# FPGA-8.net
KiCad netlist of a schematic drawn in Altium Designer
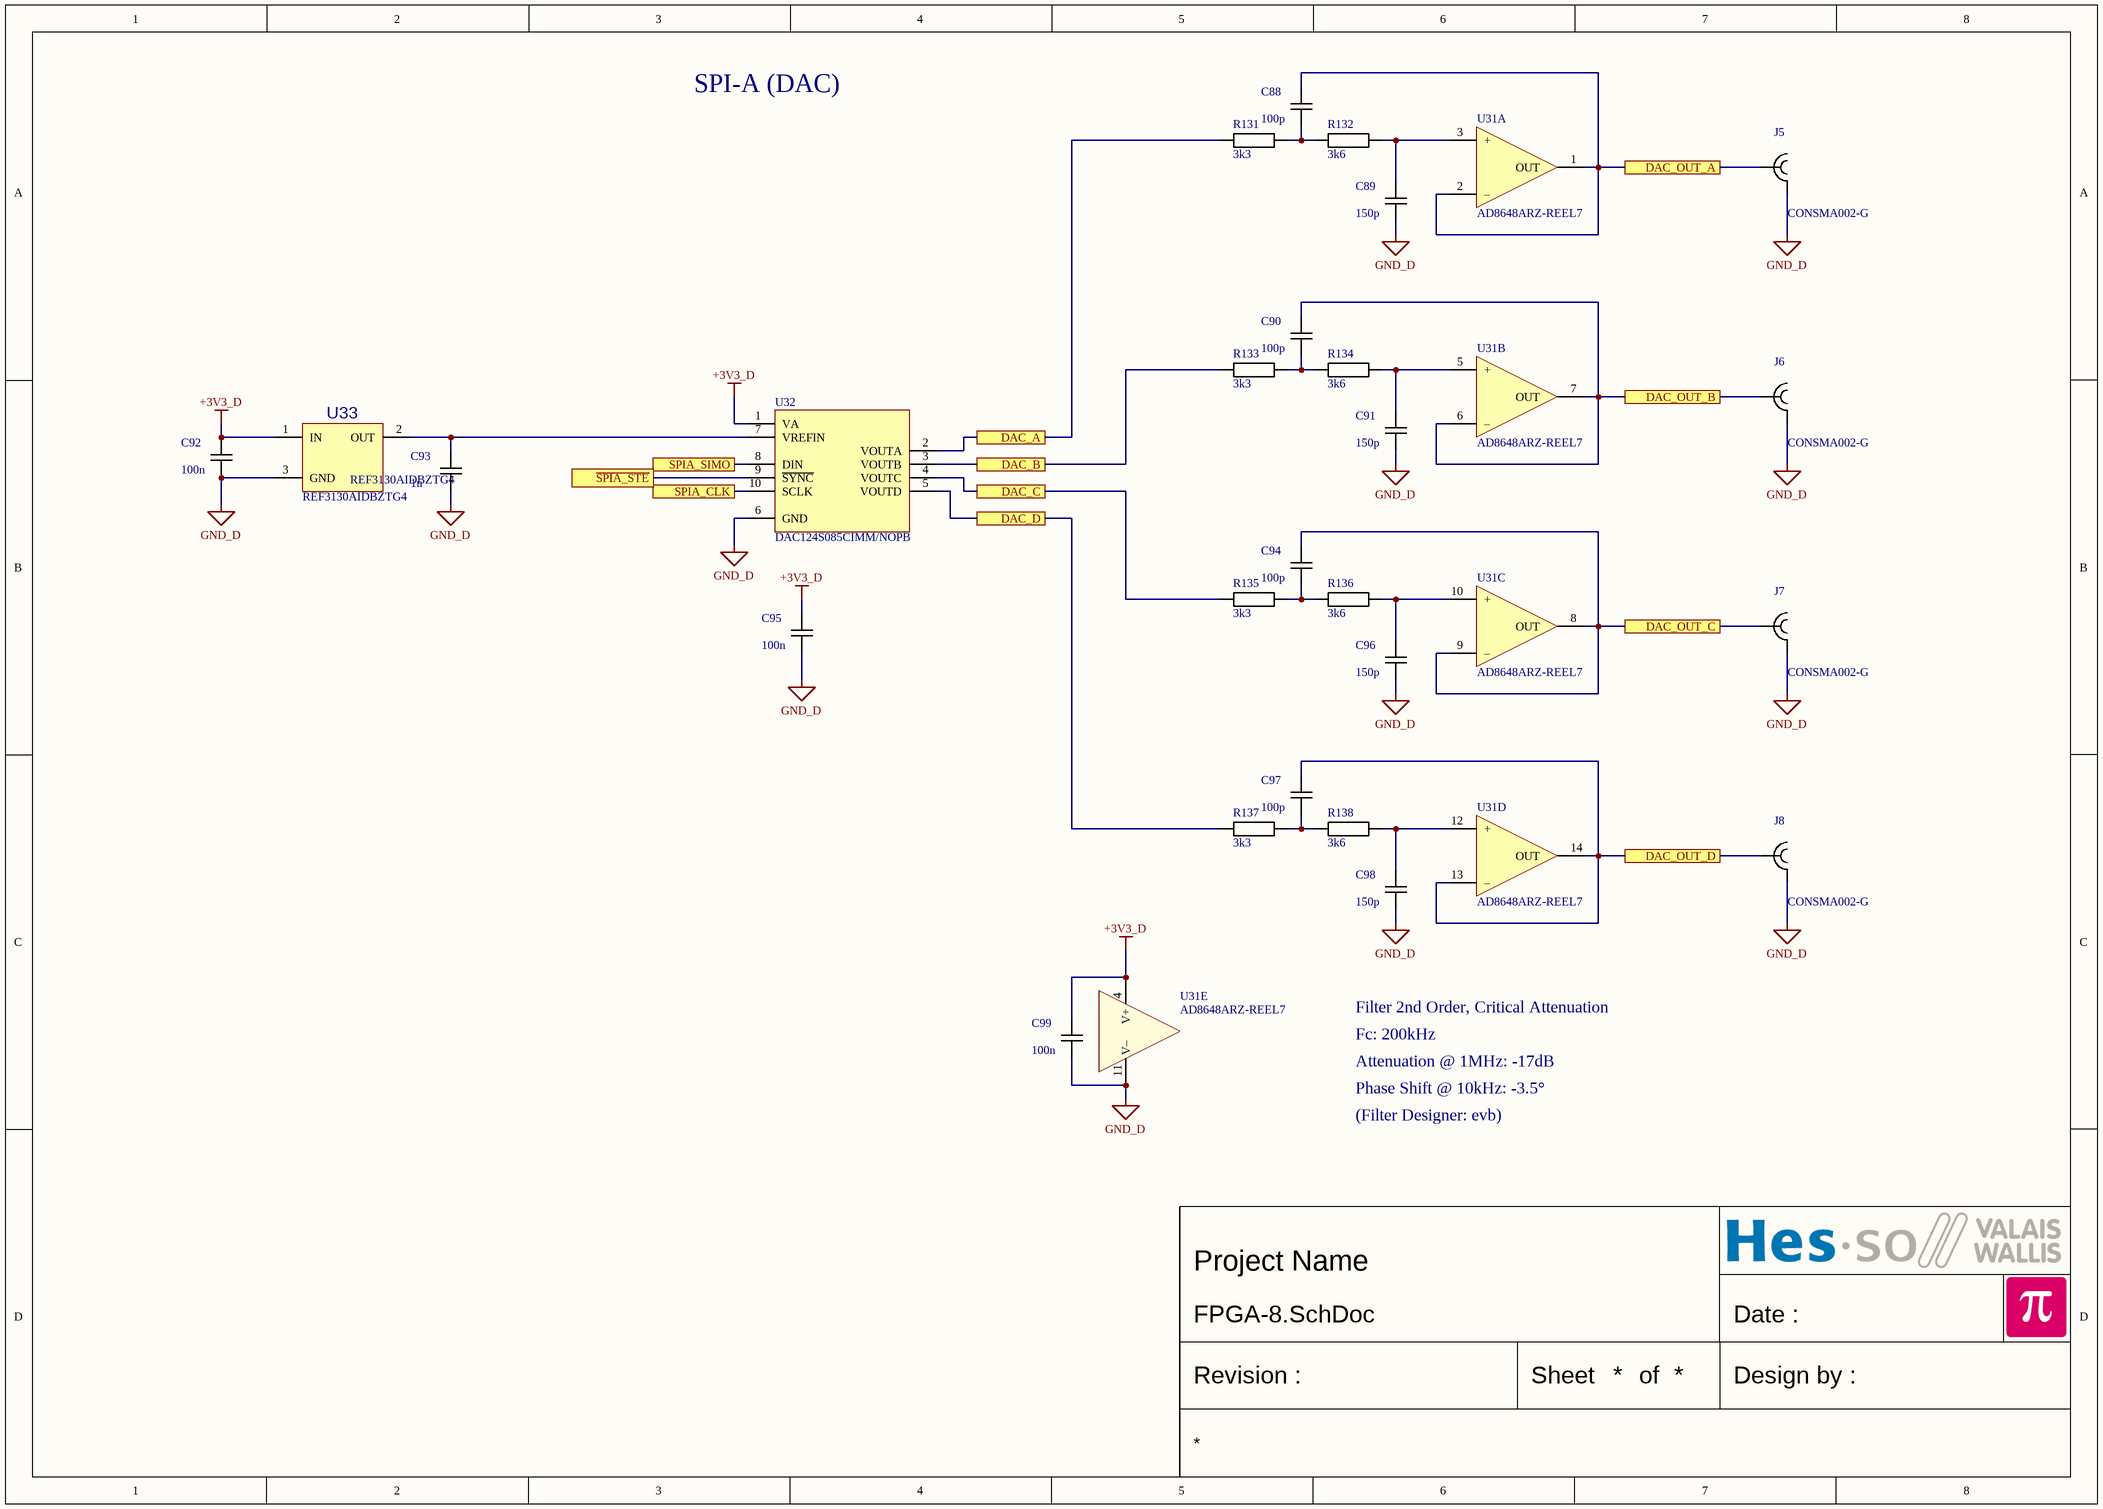
[diagram p0: FPGA-8.SchDoc]

(export (version "E")
  (design (tool "Eeschema 10.0.6"))
  (components
    (comp (ref "C88")
      (value "100p")
      (footprint "CAPACITOR 2012 REFLOW")
      (description "Capacitor X7R 10% 50V 2012(0805)")
      (libsource (lib "Capacitor") (part "Capacitor"))
    )
    (comp (ref "C89")
      (value "150p")
      (footprint "CAPACITOR 2012 REFLOW")
      (description "Capacitor X7R 10% 50V 2012(0805)")
      (libsource (lib "Capacitor") (part "Capacitor"))
    )
    (comp (ref "C90")
      (value "100p")
      (footprint "CAPACITOR 2012 REFLOW")
      (description "Capacitor X7R 10% 50V 2012(0805)")
      (libsource (lib "Capacitor") (part "Capacitor"))
    )
    (comp (ref "C91")
      (value "150p")
      (footprint "CAPACITOR 2012 REFLOW")
      (description "Capacitor X7R 10% 50V 2012(0805)")
      (libsource (lib "Capacitor") (part "Capacitor"))
    )
    (comp (ref "C92")
      (value "100n")
      (footprint "CAPACITOR 2012 REFLOW")
      (description "Capacitor X7R 10% 50V 2012(0805)")
      (libsource (lib "Capacitor") (part "Capacitor"))
    )
    (comp (ref "C93")
      (value "1u")
      (footprint "CAPACITOR 2012 REFLOW")
      (description "Capacitor X7R 10% 10V 2012(0805)")
      (libsource (lib "Capacitor") (part "Capacitor"))
    )
    (comp (ref "C94")
      (value "100p")
      (footprint "CAPACITOR 2012 REFLOW")
      (description "Capacitor X7R 10% 50V 2012(0805)")
      (libsource (lib "Capacitor") (part "Capacitor"))
    )
    (comp (ref "C95")
      (value "100n")
      (footprint "CAPACITOR 1608 REFLOW")
      (description "Capacitor X7R 10% 50V 1608(0603)")
      (libsource (lib "Capacitor") (part "Capacitor"))
    )
    (comp (ref "C96")
      (value "150p")
      (footprint "CAPACITOR 2012 REFLOW")
      (description "Capacitor X7R 10% 50V 2012(0805)")
      (libsource (lib "Capacitor") (part "Capacitor"))
    )
    (comp (ref "C97")
      (value "100p")
      (footprint "CAPACITOR 2012 REFLOW")
      (description "Capacitor X7R 10% 50V 2012(0805)")
      (libsource (lib "Capacitor") (part "Capacitor"))
    )
    (comp (ref "C98")
      (value "150p")
      (footprint "CAPACITOR 2012 REFLOW")
      (description "Capacitor X7R 10% 50V 2012(0805)")
      (libsource (lib "Capacitor") (part "Capacitor"))
    )
    (comp (ref "C99")
      (value "100n")
      (footprint "CAPACITOR 1608 REFLOW")
      (description "Capacitor X7R 10% 50V 1608(0603)")
      (libsource (lib "Capacitor") (part "Capacitor"))
    )
    (comp (ref "J5")
      (value "CONSMA002-G")
      (footprint "SMA TH Right Angle Linx CONSMA002")
      (description "SMA TH RIGHT ANGLE LINX CONSMA002")
      (fields (field (name "MANUFACTURER") "Linx Technologies"))
      (libsource (lib "Connector") (part "SMA TH RIGHT ANGLE LINX CONSMA002"))
    )
    (comp (ref "J6")
      (value "CONSMA002-G")
      (footprint "SMA TH Right Angle Linx CONSMA002")
      (description "SMA TH RIGHT ANGLE LINX CONSMA002")
      (fields (field (name "MANUFACTURER") "Linx Technologies"))
      (libsource (lib "Connector") (part "SMA TH RIGHT ANGLE LINX CONSMA002"))
    )
    (comp (ref "J7")
      (value "CONSMA002-G")
      (footprint "SMA TH Right Angle Linx CONSMA002")
      (description "SMA TH RIGHT ANGLE LINX CONSMA002")
      (fields (field (name "MANUFACTURER") "Linx Technologies"))
      (libsource (lib "Connector") (part "SMA TH RIGHT ANGLE LINX CONSMA002"))
    )
    (comp (ref "J8")
      (value "CONSMA002-G")
      (footprint "SMA TH Right Angle Linx CONSMA002")
      (description "SMA TH RIGHT ANGLE LINX CONSMA002")
      (fields (field (name "MANUFACTURER") "Linx Technologies"))
      (libsource (lib "Connector") (part "SMA TH RIGHT ANGLE LINX CONSMA002"))
    )
    (comp (ref "R131")
      (value "3k3")
      (footprint "RESISTOR 2012 REFLOW")
      (description "Resistor 1% 50V 125mW 2012(0805)")
      (libsource (lib "Resistor") (part "Resistor"))
    )
    (comp (ref "R132")
      (value "3k6")
      (footprint "RESISTOR 2012 REFLOW")
      (description "Resistor 1% 50V 125mW 2012(0805)")
      (libsource (lib "Resistor") (part "Resistor"))
    )
    (comp (ref "R133")
      (value "3k3")
      (footprint "RESISTOR 2012 REFLOW")
      (description "Resistor 1% 50V 125mW 2012(0805)")
      (libsource (lib "Resistor") (part "Resistor"))
    )
    (comp (ref "R134")
      (value "3k6")
      (footprint "RESISTOR 2012 REFLOW")
      (description "Resistor 1% 50V 125mW 2012(0805)")
      (libsource (lib "Resistor") (part "Resistor"))
    )
    (comp (ref "R135")
      (value "3k3")
      (footprint "RESISTOR 2012 REFLOW")
      (description "Resistor 1% 50V 125mW 2012(0805)")
      (libsource (lib "Resistor") (part "Resistor"))
    )
    (comp (ref "R136")
      (value "3k6")
      (footprint "RESISTOR 2012 REFLOW")
      (description "Resistor 1% 50V 125mW 2012(0805)")
      (libsource (lib "Resistor") (part "Resistor"))
    )
    (comp (ref "R137")
      (value "3k3")
      (footprint "RESISTOR 2012 REFLOW")
      (description "Resistor 1% 50V 125mW 2012(0805)")
      (libsource (lib "Resistor") (part "Resistor"))
    )
    (comp (ref "R138")
      (value "3k6")
      (footprint "RESISTOR 2012 REFLOW")
      (description "Resistor 1% 50V 125mW 2012(0805)")
      (libsource (lib "Resistor") (part "Resistor"))
    )
    (comp (ref "U31")
      (value "AD8648ARZ-REEL7")
      (footprint "SO14 P1.27 C4.0X8.8 H1.75")
      (description "Generic quad OPA 14 pins")
      (fields (field (name "MANUFACTURER") "Analog Devices"))
      (libsource (lib "Amplifier") (part "OPA QUAD"))
    )
    (comp (ref "U32")
      (value "DAC124S085CIMM/NOPB")
      (footprint "VSSOP10 P0.5 C3.1X3.1 H1.1")
      (description "DAC124S085 12-Bit Micro Power Quad Digital-to-Analog Converter With Rail-to-Rail Output")
      (fields (field (name "MANUFACTURER") "Texas Instruments"))
      (libsource (lib "Converter") (part "DAC124S085CIMM"))
    )
    (comp (ref "U33")
      (value "REF3130AIDBZTG4")
      (footprint "SOT23 P0.95 C1.6x3.0 H1.3")
      (description "Generic Positive Voltage Reference")
      (fields
        (field (name "ALTIUM_VALUE") "REF3130AIDBZTG4")
        (field (name "MANUFACTURER") "Texas Instruments")
      )
      (libsource (lib "Regulator") (part "REFERENCE SOT23 IN-OUT- GND"))
    )
  )
  (nets
    (net (code "1") (name "+3V3_D") (class "Default")
      (node (ref "C92") (pin "2") (pinfunction "2_2") (pintype "passive"))
      (node (ref "C95") (pin "2") (pinfunction "2_2") (pintype "passive"))
      (node (ref "C99") (pin "2") (pinfunction "2_2") (pintype "passive"))
      (node (ref "U31") (pin "4") (pinfunction "V+_4") (pintype "passive"))
      (node (ref "U32") (pin "1") (pinfunction "VA_1") (pintype "passive"))
      (node (ref "U33") (pin "1") (pinfunction "IN_1") (pintype "passive"))
    )
    (net (code "2") (name "/DAC_A") (class "Default")
      (node (ref "R131") (pin "1") (pinfunction "1_1") (pintype "passive"))
      (node (ref "U32") (pin "2") (pinfunction "VOUTA_2") (pintype "passive"))
    )
    (net (code "3") (name "/DAC_B") (class "Default")
      (node (ref "R133") (pin "1") (pinfunction "1_1") (pintype "passive"))
      (node (ref "U32") (pin "3") (pinfunction "VOUTB_3") (pintype "passive"))
    )
    (net (code "4") (name "/DAC_C") (class "Default")
      (node (ref "R135") (pin "1") (pinfunction "1_1") (pintype "passive"))
      (node (ref "U32") (pin "4") (pinfunction "VOUTC_4") (pintype "passive"))
    )
    (net (code "5") (name "/DAC_D") (class "Default")
      (node (ref "R137") (pin "1") (pinfunction "1_1") (pintype "passive"))
      (node (ref "U32") (pin "5") (pinfunction "VOUTD_5") (pintype "passive"))
    )
    (net (code "6") (name "/DAC_OUT_A") (class "Default")
      (node (ref "C88") (pin "2") (pinfunction "2_2") (pintype "passive"))
      (node (ref "J5") (pin "1") (pinfunction "1_1") (pintype "passive"))
      (node (ref "U31") (pin "1") (pinfunction "OUT_1") (pintype "passive"))
      (node (ref "U31") (pin "2") (pinfunction "–_2") (pintype "passive"))
    )
    (net (code "7") (name "/DAC_OUT_B") (class "Default")
      (node (ref "C90") (pin "2") (pinfunction "2_2") (pintype "passive"))
      (node (ref "J6") (pin "1") (pinfunction "1_1") (pintype "passive"))
      (node (ref "U31") (pin "6") (pinfunction "–_6") (pintype "passive"))
      (node (ref "U31") (pin "7") (pinfunction "OUT_7") (pintype "passive"))
    )
    (net (code "8") (name "/DAC_OUT_C") (class "Default")
      (node (ref "C94") (pin "2") (pinfunction "2_2") (pintype "passive"))
      (node (ref "J7") (pin "1") (pinfunction "1_1") (pintype "passive"))
      (node (ref "U31") (pin "8") (pinfunction "OUT_8") (pintype "passive"))
      (node (ref "U31") (pin "9") (pinfunction "–_9") (pintype "passive"))
    )
    (net (code "9") (name "/DAC_OUT_D") (class "Default")
      (node (ref "C97") (pin "2") (pinfunction "2_2") (pintype "passive"))
      (node (ref "J8") (pin "1") (pinfunction "1_1") (pintype "passive"))
      (node (ref "U31") (pin "13") (pinfunction "–_13") (pintype "passive"))
      (node (ref "U31") (pin "14") (pinfunction "OUT_14") (pintype "passive"))
    )
    (net (code "10") (name "/SPIA_CLK") (class "Default")
      (node (ref "U32") (pin "10") (pinfunction "SCLK_10") (pintype "passive"))
    )
    (net (code "11") (name "/SPIA_SIMO") (class "Default")
      (node (ref "U32") (pin "8") (pinfunction "DIN_8") (pintype "passive"))
    )
    (net (code "12") (name "/~{SPIA_STE}") (class "Default")
      (node (ref "U32") (pin "9") (pinfunction "~{SYNC}_9") (pintype "passive"))
    )
    (net (code "13") (name "GND_D") (class "Default")
      (node (ref "C89") (pin "1") (pinfunction "1_1") (pintype "passive"))
      (node (ref "C91") (pin "1") (pinfunction "1_1") (pintype "passive"))
      (node (ref "C92") (pin "1") (pinfunction "1_1") (pintype "passive"))
      (node (ref "C93") (pin "1") (pinfunction "1_1") (pintype "passive"))
      (node (ref "C95") (pin "1") (pinfunction "1_1") (pintype "passive"))
      (node (ref "C96") (pin "1") (pinfunction "1_1") (pintype "passive"))
      (node (ref "C98") (pin "1") (pinfunction "1_1") (pintype "passive"))
      (node (ref "C99") (pin "1") (pinfunction "1_1") (pintype "passive"))
      (node (ref "J5") (pin "2") (pinfunction "2_2") (pintype "passive"))
      (node (ref "J6") (pin "2") (pinfunction "2_2") (pintype "passive"))
      (node (ref "J7") (pin "2") (pinfunction "2_2") (pintype "passive"))
      (node (ref "J8") (pin "2") (pinfunction "2_2") (pintype "passive"))
      (node (ref "U31") (pin "11") (pinfunction "V–_11") (pintype "passive"))
      (node (ref "U32") (pin "6") (pinfunction "GND_6") (pintype "passive"))
      (node (ref "U33") (pin "3") (pinfunction "GND_3") (pintype "passive"))
    )
    (net (code "14") (name "Net-(C88-Pad1)") (class "Default")
      (node (ref "C88") (pin "1") (pinfunction "1_1") (pintype "passive"))
      (node (ref "R131") (pin "2") (pinfunction "2_2") (pintype "passive"))
      (node (ref "R132") (pin "1") (pinfunction "1_1") (pintype "passive"))
    )
    (net (code "15") (name "Net-(C90-Pad1)") (class "Default")
      (node (ref "C90") (pin "1") (pinfunction "1_1") (pintype "passive"))
      (node (ref "R133") (pin "2") (pinfunction "2_2") (pintype "passive"))
      (node (ref "R134") (pin "1") (pinfunction "1_1") (pintype "passive"))
    )
    (net (code "16") (name "Net-(C94-Pad1)") (class "Default")
      (node (ref "C94") (pin "1") (pinfunction "1_1") (pintype "passive"))
      (node (ref "R135") (pin "2") (pinfunction "2_2") (pintype "passive"))
      (node (ref "R136") (pin "1") (pinfunction "1_1") (pintype "passive"))
    )
    (net (code "17") (name "Net-(C97-Pad1)") (class "Default")
      (node (ref "C97") (pin "1") (pinfunction "1_1") (pintype "passive"))
      (node (ref "R137") (pin "2") (pinfunction "2_2") (pintype "passive"))
      (node (ref "R138") (pin "1") (pinfunction "1_1") (pintype "passive"))
    )
    (net (code "18") (name "Net-(U31A-+)") (class "Default")
      (node (ref "C89") (pin "2") (pinfunction "2_2") (pintype "passive"))
      (node (ref "R132") (pin "2") (pinfunction "2_2") (pintype "passive"))
      (node (ref "U31") (pin "3") (pinfunction "+_3") (pintype "passive"))
    )
    (net (code "19") (name "Net-(U31B-+)") (class "Default")
      (node (ref "C91") (pin "2") (pinfunction "2_2") (pintype "passive"))
      (node (ref "R134") (pin "2") (pinfunction "2_2") (pintype "passive"))
      (node (ref "U31") (pin "5") (pinfunction "+_5") (pintype "passive"))
    )
    (net (code "20") (name "Net-(U31C-+)") (class "Default")
      (node (ref "C96") (pin "2") (pinfunction "2_2") (pintype "passive"))
      (node (ref "R136") (pin "2") (pinfunction "2_2") (pintype "passive"))
      (node (ref "U31") (pin "10") (pinfunction "+_10") (pintype "passive"))
    )
    (net (code "21") (name "Net-(U31D-+)") (class "Default")
      (node (ref "C98") (pin "2") (pinfunction "2_2") (pintype "passive"))
      (node (ref "R138") (pin "2") (pinfunction "2_2") (pintype "passive"))
      (node (ref "U31") (pin "12") (pinfunction "+_12") (pintype "passive"))
    )
    (net (code "22") (name "Net-(U32-VREFIN)") (class "Default")
      (node (ref "C93") (pin "2") (pinfunction "2_2") (pintype "passive"))
      (node (ref "U32") (pin "7") (pinfunction "VREFIN_7") (pintype "passive"))
      (node (ref "U33") (pin "2") (pinfunction "OUT_2") (pintype "passive"))
    )
  )
)
